# detection_input.net
KiCad netlist of a schematic drawn in EAGLE
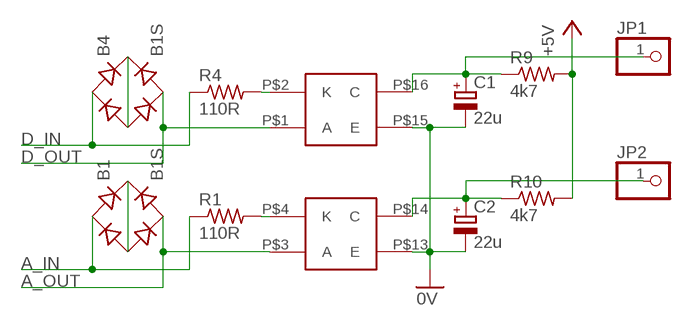
[diagram p0: schematic, sheet 1]

(export (version "E")
  (design (tool "Eeschema 10.0.6"))
  (components
    (comp (ref "B1")
      (value "B1S")
      (footprint "eagle-import:MBS")
      (libsource (lib "eagle-import") (part "BS1"))
    )
    (comp (ref "B4")
      (value "B1S")
      (footprint "eagle-import:MBS")
      (libsource (lib "eagle-import") (part "BS1"))
    )
    (comp (ref "C1")
      (value "22u")
      (footprint "eagle-import:E2-4")
      (libsource (lib "eagle-import") (part "CPOL-EUE2-4"))
    )
    (comp (ref "C2")
      (value "22u")
      (footprint "eagle-import:E2-4")
      (libsource (lib "eagle-import") (part "CPOL-EUE2-4"))
    )
    (comp (ref "JP1")
      (value "PINHD-1X1")
      (footprint "eagle-import:1X01")
      (libsource (lib "eagle-import") (part "PINHD-1X1"))
    )
    (comp (ref "JP2")
      (value "PINHD-1X1")
      (footprint "eagle-import:1X01")
      (libsource (lib "eagle-import") (part "PINHD-1X1"))
    )
    (comp (ref "R1")
      (value "110R")
      (footprint "eagle-import:R0805")
      (libsource (lib "eagle-import") (part "R-US_R0805"))
    )
    (comp (ref "R4")
      (value "110R")
      (footprint "eagle-import:R0805")
      (libsource (lib "eagle-import") (part "R-US_R0805"))
    )
    (comp (ref "R9")
      (value "4k7")
      (footprint "eagle-import:R0805")
      (libsource (lib "eagle-import") (part "R-US_R0805"))
    )
    (comp (ref "R10")
      (value "4k7")
      (footprint "eagle-import:R0805")
      (libsource (lib "eagle-import") (part "R-US_R0805"))
    )
    (comp (ref "U$1")
      (value "ILQ620D")
      (footprint "eagle-import:ILQ620D")
      (libsource (lib "eagle-import") (part "ILQ620D"))
    )
  )
  (nets
    (net (code "1") (name "+5V") (class "Default")
      (node (ref "R10") (pin "2") (pinfunction "2_2") (pintype "passive"))
      (node (ref "R9") (pin "2") (pinfunction "2_2") (pintype "passive"))
    )
    (net (code "2") (name "/A_IN") (class "Default")
      (node (ref "B1") (pin "AC1") (pinfunction "AC1_AC1") (pintype "passive"))
      (node (ref "R1") (pin "1") (pinfunction "1_1") (pintype "passive"))
    )
    (net (code "3") (name "/A_OUT") (class "Default")
      (node (ref "B1") (pin "AC2") (pinfunction "AC2_AC2") (pintype "passive"))
      (node (ref "U$1") (pin "P$3") (pinfunction "A_P$3") (pintype "bidirectional"))
    )
    (net (code "4") (name "/D_IN") (class "Default")
      (node (ref "B4") (pin "AC1") (pinfunction "AC1_AC1") (pintype "passive"))
      (node (ref "R4") (pin "1") (pinfunction "1_1") (pintype "passive"))
    )
    (net (code "5") (name "/D_OUT") (class "Default")
      (node (ref "B4") (pin "AC2") (pinfunction "AC2_AC2") (pintype "passive"))
      (node (ref "U$1") (pin "P$1") (pinfunction "A_P$1") (pintype "bidirectional"))
    )
    (net (code "6") (name "0V") (class "Default")
      (node (ref "C1") (pin "-") (pinfunction "-_-") (pintype "passive"))
      (node (ref "C2") (pin "-") (pinfunction "-_-") (pintype "passive"))
      (node (ref "U$1") (pin "P$13") (pinfunction "E_P$13") (pintype "bidirectional"))
      (node (ref "U$1") (pin "P$15") (pinfunction "E_P$15") (pintype "bidirectional"))
    )
    (net (code "7") (name "Net-(B1-Pad+)") (class "Default")
      (node (ref "B1") (pin "+") (pinfunction "+_+") (pintype "passive"))
      (node (ref "B1") (pin "-") (pinfunction "-_-") (pintype "passive"))
    )
    (net (code "8") (name "Net-(B4-Pad+)") (class "Default")
      (node (ref "B4") (pin "+") (pinfunction "+_+") (pintype "passive"))
      (node (ref "B4") (pin "-") (pinfunction "-_-") (pintype "passive"))
    )
    (net (code "9") (name "Net-(U$1A-C)") (class "Default")
      (node (ref "C1") (pin "+") (pinfunction "+_+") (pintype "passive"))
      (node (ref "JP1") (pin "1") (pinfunction "1_1") (pintype "passive"))
      (node (ref "R9") (pin "1") (pinfunction "1_1") (pintype "passive"))
      (node (ref "U$1") (pin "P$16") (pinfunction "C_P$16") (pintype "bidirectional"))
    )
    (net (code "10") (name "Net-(U$1A-K)") (class "Default")
      (node (ref "R4") (pin "2") (pinfunction "2_2") (pintype "passive"))
      (node (ref "U$1") (pin "P$2") (pinfunction "K_P$2") (pintype "bidirectional"))
    )
    (net (code "11") (name "Net-(U$1B-C)") (class "Default")
      (node (ref "C2") (pin "+") (pinfunction "+_+") (pintype "passive"))
      (node (ref "JP2") (pin "1") (pinfunction "1_1") (pintype "passive"))
      (node (ref "R10") (pin "1") (pinfunction "1_1") (pintype "passive"))
      (node (ref "U$1") (pin "P$14") (pinfunction "C_P$14") (pintype "bidirectional"))
    )
    (net (code "12") (name "Net-(U$1B-K)") (class "Default")
      (node (ref "R1") (pin "2") (pinfunction "2_2") (pintype "passive"))
      (node (ref "U$1") (pin "P$4") (pinfunction "K_P$4") (pintype "bidirectional"))
    )
  )
)
